# escv1.net
KiCad netlist of a schematic drawn in EAGLE
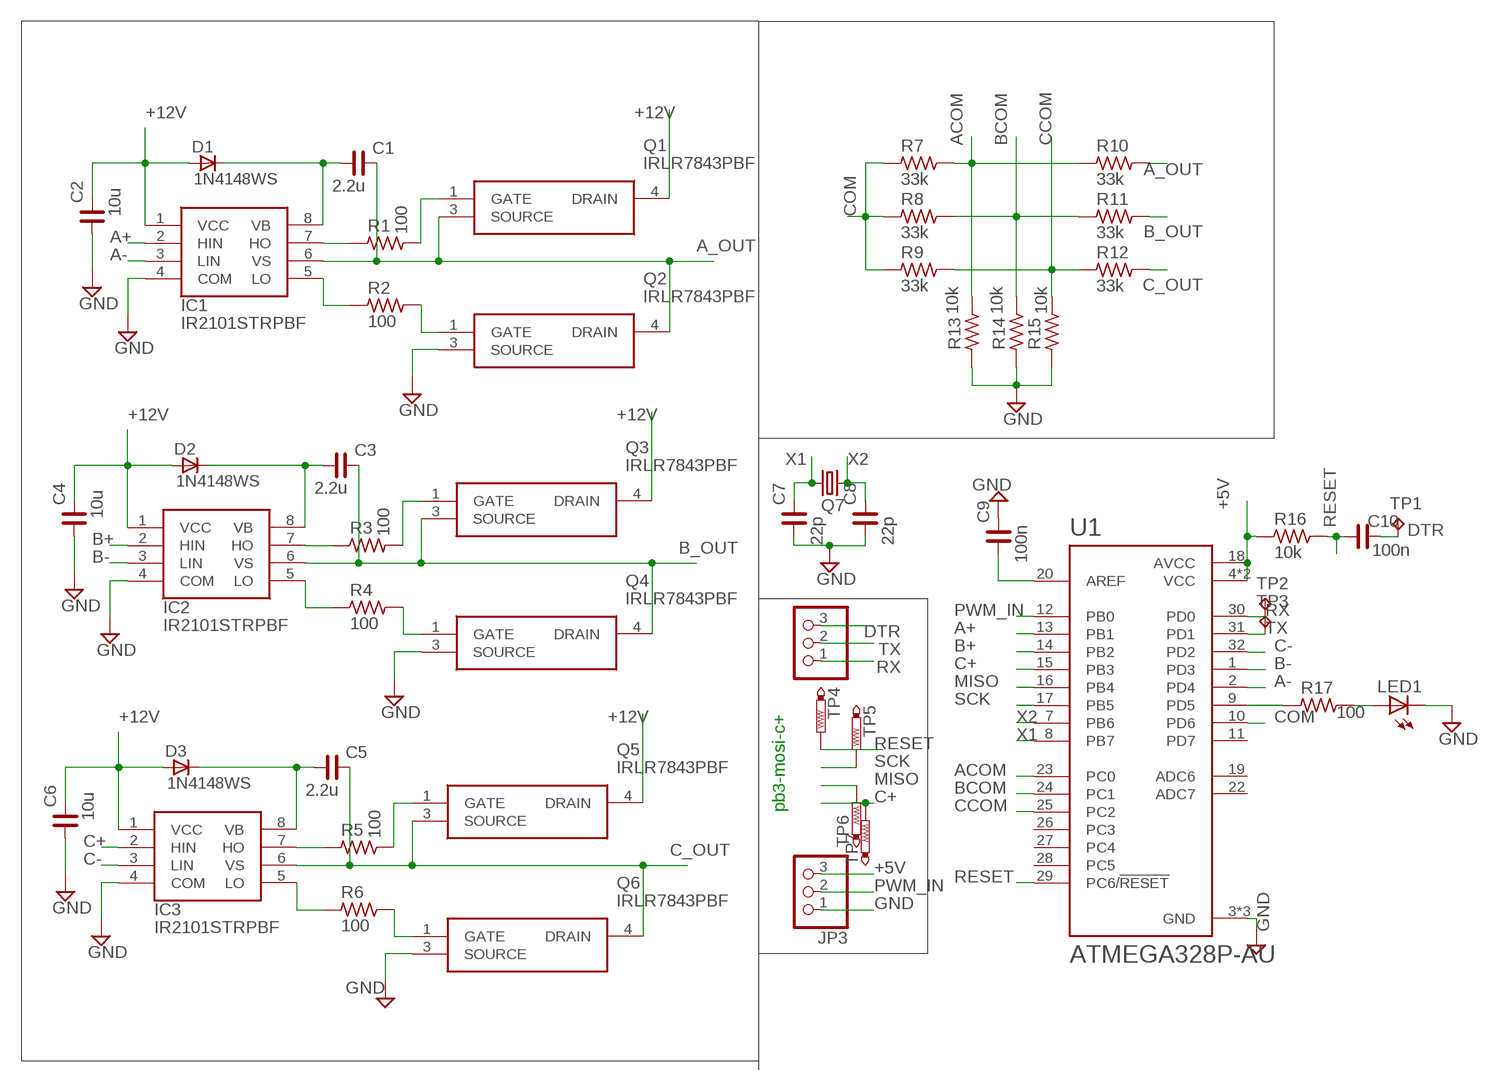
[diagram p0: schematic, sheet 1]

(export (version "E")
  (design (tool "Eeschema 10.0.6"))
  (components
    (comp (ref "C1")
      (value "2.2u")
      (footprint "eagle-import:C2012")
      (libsource (lib "eagle-import") (part "C_2012"))
    )
    (comp (ref "C2")
      (value "10u")
      (footprint "eagle-import:C2012")
      (libsource (lib "eagle-import") (part "C_2012"))
    )
    (comp (ref "C3")
      (value "2.2u")
      (footprint "eagle-import:C2012")
      (libsource (lib "eagle-import") (part "C_2012"))
    )
    (comp (ref "C4")
      (value "10u")
      (footprint "eagle-import:C2012")
      (libsource (lib "eagle-import") (part "C_2012"))
    )
    (comp (ref "C5")
      (value "2.2u")
      (footprint "eagle-import:C2012")
      (libsource (lib "eagle-import") (part "C_2012"))
    )
    (comp (ref "C6")
      (value "10u")
      (footprint "eagle-import:C2012")
      (libsource (lib "eagle-import") (part "C_2012"))
    )
    (comp (ref "C7")
      (value "22p")
      (footprint "eagle-import:C2012")
      (libsource (lib "eagle-import") (part "C_2012"))
    )
    (comp (ref "C8")
      (value "22p")
      (footprint "eagle-import:C2012")
      (libsource (lib "eagle-import") (part "C_2012"))
    )
    (comp (ref "C9")
      (value "100n")
      (footprint "eagle-import:C2012")
      (libsource (lib "eagle-import") (part "C_2012"))
    )
    (comp (ref "C10")
      (value "100n")
      (footprint "eagle-import:C2012")
      (libsource (lib "eagle-import") (part "C_2012"))
    )
    (comp (ref "D1")
      (value "1N4148WS")
      (footprint "eagle-import:SOD323F")
      (libsource (lib "eagle-import") (part "1N4148WS"))
    )
    (comp (ref "D2")
      (value "1N4148WS")
      (footprint "eagle-import:SOD323F")
      (libsource (lib "eagle-import") (part "1N4148WS"))
    )
    (comp (ref "D3")
      (value "1N4148WS")
      (footprint "eagle-import:SOD323F")
      (libsource (lib "eagle-import") (part "1N4148WS"))
    )
    (comp (ref "IC1")
      (value "IR2101STRPBF")
      (footprint "eagle-import:SOIC127P600X175-8N")
      (fields (field (name "MOUSER_PART_NUMBER") "942-IR2101STRPBF"))
      (libsource (lib "eagle-import") (part "IR2101STRPBF"))
    )
    (comp (ref "IC2")
      (value "IR2101STRPBF")
      (footprint "eagle-import:SOIC127P600X175-8N")
      (fields (field (name "MOUSER_PART_NUMBER") "942-IR2101STRPBF"))
      (libsource (lib "eagle-import") (part "IR2101STRPBF"))
    )
    (comp (ref "IC3")
      (value "IR2101STRPBF")
      (footprint "eagle-import:SOIC127P600X175-8N")
      (fields (field (name "MOUSER_PART_NUMBER") "942-IR2101STRPBF"))
      (libsource (lib "eagle-import") (part "IR2101STRPBF"))
    )
    (comp (ref "JP1")
      (value "PINHD-1X3")
      (footprint "eagle-import:1X03")
      (libsource (lib "eagle-import") (part "PINHD-1X3"))
    )
    (comp (ref "JP3")
      (value "PINHD-1X3")
      (footprint "eagle-import:1X03")
      (libsource (lib "eagle-import") (part "PINHD-1X3"))
    )
    (comp (ref "LED1")
      (value "LEDCHIP-LED0805")
      (footprint "eagle-import:CHIP-LED0805")
      (libsource (lib "eagle-import") (part "LEDCHIP-LED0805"))
    )
    (comp (ref "Q1")
      (value "IRLR7843PBF")
      (footprint "eagle-import:D-PAK(TO-252AA)_1")
      (fields (field (name "MOUSER_PART_NUMBER") "942-IRLR7843PBF"))
      (libsource (lib "eagle-import") (part "IRLR7843PBF"))
    )
    (comp (ref "Q2")
      (value "IRLR7843PBF")
      (footprint "eagle-import:D-PAK(TO-252AA)_1")
      (fields (field (name "MOUSER_PART_NUMBER") "942-IRLR7843PBF"))
      (libsource (lib "eagle-import") (part "IRLR7843PBF"))
    )
    (comp (ref "Q3")
      (value "IRLR7843PBF")
      (footprint "eagle-import:D-PAK(TO-252AA)_1")
      (fields (field (name "MOUSER_PART_NUMBER") "942-IRLR7843PBF"))
      (libsource (lib "eagle-import") (part "IRLR7843PBF"))
    )
    (comp (ref "Q4")
      (value "IRLR7843PBF")
      (footprint "eagle-import:D-PAK(TO-252AA)_1")
      (fields (field (name "MOUSER_PART_NUMBER") "942-IRLR7843PBF"))
      (libsource (lib "eagle-import") (part "IRLR7843PBF"))
    )
    (comp (ref "Q5")
      (value "IRLR7843PBF")
      (footprint "eagle-import:D-PAK(TO-252AA)_1")
      (fields (field (name "MOUSER_PART_NUMBER") "942-IRLR7843PBF"))
      (libsource (lib "eagle-import") (part "IRLR7843PBF"))
    )
    (comp (ref "Q6")
      (value "IRLR7843PBF")
      (footprint "eagle-import:D-PAK(TO-252AA)_1")
      (fields (field (name "MOUSER_PART_NUMBER") "942-IRLR7843PBF"))
      (libsource (lib "eagle-import") (part "IRLR7843PBF"))
    )
    (comp (ref "Q7")
      (value "CRYSTALSM49")
      (footprint "eagle-import:SM49")
      (libsource (lib "eagle-import") (part "CRYSTALSM49"))
    )
    (comp (ref "R1")
      (value "100")
      (footprint "eagle-import:R2012")
      (libsource (lib "eagle-import") (part "R_2012"))
    )
    (comp (ref "R2")
      (value "100")
      (footprint "eagle-import:R2012")
      (libsource (lib "eagle-import") (part "R_2012"))
    )
    (comp (ref "R3")
      (value "100")
      (footprint "eagle-import:R2012")
      (libsource (lib "eagle-import") (part "R_2012"))
    )
    (comp (ref "R4")
      (value "100")
      (footprint "eagle-import:R2012")
      (libsource (lib "eagle-import") (part "R_2012"))
    )
    (comp (ref "R5")
      (value "100")
      (footprint "eagle-import:R2012")
      (libsource (lib "eagle-import") (part "R_2012"))
    )
    (comp (ref "R6")
      (value "100")
      (footprint "eagle-import:R2012")
      (libsource (lib "eagle-import") (part "R_2012"))
    )
    (comp (ref "R7")
      (value "33k")
      (footprint "eagle-import:R2012")
      (libsource (lib "eagle-import") (part "R_2012"))
    )
    (comp (ref "R8")
      (value "33k")
      (footprint "eagle-import:R2012")
      (libsource (lib "eagle-import") (part "R_2012"))
    )
    (comp (ref "R9")
      (value "33k")
      (footprint "eagle-import:R2012")
      (libsource (lib "eagle-import") (part "R_2012"))
    )
    (comp (ref "R10")
      (value "33k")
      (footprint "eagle-import:R2012")
      (libsource (lib "eagle-import") (part "R_2012"))
    )
    (comp (ref "R11")
      (value "33k")
      (footprint "eagle-import:R2012")
      (libsource (lib "eagle-import") (part "R_2012"))
    )
    (comp (ref "R12")
      (value "33k")
      (footprint "eagle-import:R2012")
      (libsource (lib "eagle-import") (part "R_2012"))
    )
    (comp (ref "R13")
      (value "10k")
      (footprint "eagle-import:R2012")
      (libsource (lib "eagle-import") (part "R_2012"))
    )
    (comp (ref "R14")
      (value "10k")
      (footprint "eagle-import:R2012")
      (libsource (lib "eagle-import") (part "R_2012"))
    )
    (comp (ref "R15")
      (value "10k")
      (footprint "eagle-import:R2012")
      (libsource (lib "eagle-import") (part "R_2012"))
    )
    (comp (ref "R16")
      (value "10k")
      (footprint "eagle-import:R2012")
      (libsource (lib "eagle-import") (part "R_2012"))
    )
    (comp (ref "R17")
      (value "100")
      (footprint "eagle-import:R2012")
      (libsource (lib "eagle-import") (part "R_2012"))
    )
    (comp (ref "TP1")
      (value "TPTP07R")
      (footprint "eagle-import:TP07R")
      (libsource (lib "eagle-import") (part "TPTP07R"))
    )
    (comp (ref "TP2")
      (value "TPTP07R")
      (footprint "eagle-import:TP07R")
      (libsource (lib "eagle-import") (part "TPTP07R"))
    )
    (comp (ref "TP3")
      (value "TPTP07R")
      (footprint "eagle-import:TP07R")
      (libsource (lib "eagle-import") (part "TPTP07R"))
    )
    (comp (ref "TP4")
      (value "PTR1TP10R")
      (footprint "eagle-import:TP10R")
      (libsource (lib "eagle-import") (part "PTR1TP10R"))
    )
    (comp (ref "TP5")
      (value "PTR1TP10R")
      (footprint "eagle-import:TP10R")
      (libsource (lib "eagle-import") (part "PTR1TP10R"))
    )
    (comp (ref "TP6")
      (value "PTR1TP10R")
      (footprint "eagle-import:TP10R")
      (libsource (lib "eagle-import") (part "PTR1TP10R"))
    )
    (comp (ref "TP7")
      (value "PTR1TP10R")
      (footprint "eagle-import:TP10R")
      (libsource (lib "eagle-import") (part "PTR1TP10R"))
    )
    (comp (ref "U1")
      (value "ATMEGA328P-AU")
      (footprint "eagle-import:QFP80P900X900X120-32N")
      (fields (field (name "MF") "Microchip Technology"))
      (libsource (lib "eagle-import") (part "ATMEGA328P-AU"))
    )
  )
  (nets
    (net (code "1") (name "/+5V") (class "Default")
      (node (ref "JP3") (pin "3") (pinfunction "3_3") (pintype "passive"))
      (node (ref "R16") (pin "1") (pinfunction "1_1") (pintype "passive"))
      (node (ref "U1") (pin "18") (pinfunction "AVCC_18") (pintype "power_in"))
      (node (ref "U1") (pin "4") (pinfunction "VCC_4") (pintype "power_in"))
      (node (ref "U1") (pin "6") (pinfunction "VCC_6") (pintype "power_in"))
    )
    (net (code "2") (name "/+12V") (class "Default")
      (node (ref "C2") (pin "2") (pinfunction "2_2") (pintype "passive"))
      (node (ref "C4") (pin "2") (pinfunction "2_2") (pintype "passive"))
      (node (ref "C6") (pin "2") (pinfunction "2_2") (pintype "passive"))
      (node (ref "D1") (pin "A") (pinfunction "A_A") (pintype "passive"))
      (node (ref "D2") (pin "A") (pinfunction "A_A") (pintype "passive"))
      (node (ref "D3") (pin "A") (pinfunction "A_A") (pintype "passive"))
      (node (ref "IC1") (pin "1") (pinfunction "VCC_1") (pintype "bidirectional"))
      (node (ref "IC2") (pin "1") (pinfunction "VCC_1") (pintype "bidirectional"))
      (node (ref "IC3") (pin "1") (pinfunction "VCC_1") (pintype "bidirectional"))
      (node (ref "Q1") (pin "4") (pinfunction "DRAIN_4") (pintype "bidirectional"))
      (node (ref "Q3") (pin "4") (pinfunction "DRAIN_4") (pintype "bidirectional"))
      (node (ref "Q5") (pin "4") (pinfunction "DRAIN_4") (pintype "bidirectional"))
    )
    (net (code "3") (name "/A+") (class "Default")
      (node (ref "IC1") (pin "2") (pinfunction "HIN_2") (pintype "bidirectional"))
      (node (ref "U1") (pin "13") (pinfunction "PB1_13") (pintype "bidirectional"))
    )
    (net (code "4") (name "/A-") (class "Default")
      (node (ref "IC1") (pin "3") (pinfunction "LIN_3") (pintype "bidirectional"))
      (node (ref "U1") (pin "2") (pinfunction "PD4_2") (pintype "bidirectional"))
    )
    (net (code "5") (name "/ACOM") (class "Default")
      (node (ref "R10") (pin "1") (pinfunction "1_1") (pintype "passive"))
      (node (ref "R13") (pin "2") (pinfunction "2_2") (pintype "passive"))
      (node (ref "R7") (pin "2") (pinfunction "2_2") (pintype "passive"))
      (node (ref "U1") (pin "23") (pinfunction "PC0_23") (pintype "bidirectional"))
    )
    (net (code "6") (name "/A_OUT") (class "Default")
      (node (ref "C1") (pin "2") (pinfunction "2_2") (pintype "passive"))
      (node (ref "IC1") (pin "6") (pinfunction "VS_6") (pintype "bidirectional"))
      (node (ref "Q1") (pin "3") (pinfunction "SOURCE_3") (pintype "bidirectional"))
      (node (ref "Q2") (pin "4") (pinfunction "DRAIN_4") (pintype "bidirectional"))
      (node (ref "R10") (pin "2") (pinfunction "2_2") (pintype "passive"))
    )
    (net (code "7") (name "/B+") (class "Default")
      (node (ref "IC2") (pin "2") (pinfunction "HIN_2") (pintype "bidirectional"))
      (node (ref "U1") (pin "14") (pinfunction "PB2_14") (pintype "bidirectional"))
    )
    (net (code "8") (name "/B-") (class "Default")
      (node (ref "IC2") (pin "3") (pinfunction "LIN_3") (pintype "bidirectional"))
      (node (ref "U1") (pin "1") (pinfunction "PD3_1") (pintype "bidirectional"))
    )
    (net (code "9") (name "/BCOM") (class "Default")
      (node (ref "R11") (pin "1") (pinfunction "1_1") (pintype "passive"))
      (node (ref "R14") (pin "2") (pinfunction "2_2") (pintype "passive"))
      (node (ref "R8") (pin "2") (pinfunction "2_2") (pintype "passive"))
      (node (ref "U1") (pin "24") (pinfunction "PC1_24") (pintype "bidirectional"))
    )
    (net (code "10") (name "/B_OUT") (class "Default")
      (node (ref "C3") (pin "2") (pinfunction "2_2") (pintype "passive"))
      (node (ref "IC2") (pin "6") (pinfunction "VS_6") (pintype "bidirectional"))
      (node (ref "Q3") (pin "3") (pinfunction "SOURCE_3") (pintype "bidirectional"))
      (node (ref "Q4") (pin "4") (pinfunction "DRAIN_4") (pintype "bidirectional"))
      (node (ref "R11") (pin "2") (pinfunction "2_2") (pintype "passive"))
    )
    (net (code "11") (name "/C+") (class "Default")
      (node (ref "IC3") (pin "2") (pinfunction "HIN_2") (pintype "bidirectional"))
      (node (ref "TP7") (pin "TP") (pinfunction "TP_TP") (pintype "input"))
      (node (ref "U1") (pin "15") (pinfunction "PB3_15") (pintype "bidirectional"))
    )
    (net (code "12") (name "/C-") (class "Default")
      (node (ref "IC3") (pin "3") (pinfunction "LIN_3") (pintype "bidirectional"))
      (node (ref "U1") (pin "32") (pinfunction "PD2_32") (pintype "bidirectional"))
    )
    (net (code "13") (name "/CCOM") (class "Default")
      (node (ref "R12") (pin "1") (pinfunction "1_1") (pintype "passive"))
      (node (ref "R15") (pin "2") (pinfunction "2_2") (pintype "passive"))
      (node (ref "R9") (pin "2") (pinfunction "2_2") (pintype "passive"))
      (node (ref "U1") (pin "25") (pinfunction "PC2_25") (pintype "bidirectional"))
    )
    (net (code "14") (name "/COM") (class "Default")
      (node (ref "R7") (pin "1") (pinfunction "1_1") (pintype "passive"))
      (node (ref "R8") (pin "1") (pinfunction "1_1") (pintype "passive"))
      (node (ref "R9") (pin "1") (pinfunction "1_1") (pintype "passive"))
      (node (ref "U1") (pin "10") (pinfunction "PD6_10") (pintype "bidirectional"))
    )
    (net (code "15") (name "/C_OUT") (class "Default")
      (node (ref "C5") (pin "2") (pinfunction "2_2") (pintype "passive"))
      (node (ref "IC3") (pin "6") (pinfunction "VS_6") (pintype "bidirectional"))
      (node (ref "Q5") (pin "3") (pinfunction "SOURCE_3") (pintype "bidirectional"))
      (node (ref "Q6") (pin "4") (pinfunction "DRAIN_4") (pintype "bidirectional"))
      (node (ref "R12") (pin "2") (pinfunction "2_2") (pintype "passive"))
    )
    (net (code "16") (name "/DTR") (class "Default")
      (node (ref "C10") (pin "2") (pinfunction "2_2") (pintype "passive"))
      (node (ref "JP1") (pin "3") (pinfunction "3_3") (pintype "passive"))
      (node (ref "TP1") (pin "TP") (pinfunction "TP_TP") (pintype "input"))
    )
    (net (code "17") (name "/MISO") (class "Default")
      (node (ref "TP6") (pin "TP") (pinfunction "TP_TP") (pintype "input"))
      (node (ref "U1") (pin "16") (pinfunction "PB4_16") (pintype "bidirectional"))
    )
    (net (code "18") (name "/PWM_IN") (class "Default")
      (node (ref "JP3") (pin "2") (pinfunction "2_2") (pintype "passive"))
      (node (ref "U1") (pin "12") (pinfunction "PB0_12") (pintype "bidirectional"))
    )
    (net (code "19") (name "/RESET") (class "Default")
      (node (ref "C10") (pin "1") (pinfunction "1_1") (pintype "passive"))
      (node (ref "R16") (pin "2") (pinfunction "2_2") (pintype "passive"))
      (node (ref "TP4") (pin "TP") (pinfunction "TP_TP") (pintype "input"))
      (node (ref "U1") (pin "29") (pinfunction "PC6/~{RESET}_29") (pintype "bidirectional"))
    )
    (net (code "20") (name "/RX") (class "Default")
      (node (ref "JP1") (pin "1") (pinfunction "1_1") (pintype "passive"))
      (node (ref "TP2") (pin "TP") (pinfunction "TP_TP") (pintype "input"))
      (node (ref "U1") (pin "30") (pinfunction "PD0_30") (pintype "bidirectional"))
    )
    (net (code "21") (name "/SCK") (class "Default")
      (node (ref "TP5") (pin "TP") (pinfunction "TP_TP") (pintype "input"))
      (node (ref "U1") (pin "17") (pinfunction "PB5_17") (pintype "bidirectional"))
    )
    (net (code "22") (name "/TX") (class "Default")
      (node (ref "JP1") (pin "2") (pinfunction "2_2") (pintype "passive"))
      (node (ref "TP3") (pin "TP") (pinfunction "TP_TP") (pintype "input"))
      (node (ref "U1") (pin "31") (pinfunction "PD1_31") (pintype "bidirectional"))
    )
    (net (code "23") (name "/X1") (class "Default")
      (node (ref "C7") (pin "2") (pinfunction "2_2") (pintype "passive"))
      (node (ref "Q7") (pin "1") (pinfunction "1_1") (pintype "passive"))
      (node (ref "U1") (pin "8") (pinfunction "PB7_8") (pintype "bidirectional"))
    )
    (net (code "24") (name "/X2") (class "Default")
      (node (ref "C8") (pin "2") (pinfunction "2_2") (pintype "passive"))
      (node (ref "Q7") (pin "2") (pinfunction "2_2") (pintype "passive"))
      (node (ref "U1") (pin "7") (pinfunction "PB6_7") (pintype "bidirectional"))
    )
    (net (code "25") (name "GND") (class "Default")
      (node (ref "C2") (pin "1") (pinfunction "1_1") (pintype "passive"))
      (node (ref "C4") (pin "1") (pinfunction "1_1") (pintype "passive"))
      (node (ref "C6") (pin "1") (pinfunction "1_1") (pintype "passive"))
      (node (ref "C7") (pin "1") (pinfunction "1_1") (pintype "passive"))
      (node (ref "C8") (pin "1") (pinfunction "1_1") (pintype "passive"))
      (node (ref "C9") (pin "2") (pinfunction "2_2") (pintype "passive"))
      (node (ref "IC1") (pin "4") (pinfunction "COM_4") (pintype "bidirectional"))
      (node (ref "IC2") (pin "4") (pinfunction "COM_4") (pintype "bidirectional"))
      (node (ref "IC3") (pin "4") (pinfunction "COM_4") (pintype "bidirectional"))
      (node (ref "JP3") (pin "1") (pinfunction "1_1") (pintype "passive"))
      (node (ref "LED1") (pin "C") (pinfunction "C_C") (pintype "passive"))
      (node (ref "Q2") (pin "3") (pinfunction "SOURCE_3") (pintype "bidirectional"))
      (node (ref "Q4") (pin "3") (pinfunction "SOURCE_3") (pintype "bidirectional"))
      (node (ref "Q6") (pin "3") (pinfunction "SOURCE_3") (pintype "bidirectional"))
      (node (ref "R13") (pin "1") (pinfunction "1_1") (pintype "passive"))
      (node (ref "R14") (pin "1") (pinfunction "1_1") (pintype "passive"))
      (node (ref "R15") (pin "1") (pinfunction "1_1") (pintype "passive"))
      (node (ref "U1") (pin "21") (pinfunction "GND_21") (pintype "power_in"))
      (node (ref "U1") (pin "3") (pinfunction "GND_3") (pintype "power_in"))
      (node (ref "U1") (pin "5") (pinfunction "GND_5") (pintype "power_in"))
    )
    (net (code "26") (name "Net-(IC1-HO)") (class "Default")
      (node (ref "IC1") (pin "7") (pinfunction "HO_7") (pintype "bidirectional"))
      (node (ref "R1") (pin "1") (pinfunction "1_1") (pintype "passive"))
    )
    (net (code "27") (name "Net-(IC1-LO)") (class "Default")
      (node (ref "IC1") (pin "5") (pinfunction "LO_5") (pintype "bidirectional"))
      (node (ref "R2") (pin "1") (pinfunction "1_1") (pintype "passive"))
    )
    (net (code "28") (name "Net-(IC1-VB)") (class "Default")
      (node (ref "C1") (pin "1") (pinfunction "1_1") (pintype "passive"))
      (node (ref "D1") (pin "C") (pinfunction "C_C") (pintype "passive"))
      (node (ref "IC1") (pin "8") (pinfunction "VB_8") (pintype "bidirectional"))
    )
    (net (code "29") (name "Net-(IC2-HO)") (class "Default")
      (node (ref "IC2") (pin "7") (pinfunction "HO_7") (pintype "bidirectional"))
      (node (ref "R3") (pin "1") (pinfunction "1_1") (pintype "passive"))
    )
    (net (code "30") (name "Net-(IC2-LO)") (class "Default")
      (node (ref "IC2") (pin "5") (pinfunction "LO_5") (pintype "bidirectional"))
      (node (ref "R4") (pin "1") (pinfunction "1_1") (pintype "passive"))
    )
    (net (code "31") (name "Net-(IC2-VB)") (class "Default")
      (node (ref "C3") (pin "1") (pinfunction "1_1") (pintype "passive"))
      (node (ref "D2") (pin "C") (pinfunction "C_C") (pintype "passive"))
      (node (ref "IC2") (pin "8") (pinfunction "VB_8") (pintype "bidirectional"))
    )
    (net (code "32") (name "Net-(IC3-HO)") (class "Default")
      (node (ref "IC3") (pin "7") (pinfunction "HO_7") (pintype "bidirectional"))
      (node (ref "R5") (pin "1") (pinfunction "1_1") (pintype "passive"))
    )
    (net (code "33") (name "Net-(IC3-LO)") (class "Default")
      (node (ref "IC3") (pin "5") (pinfunction "LO_5") (pintype "bidirectional"))
      (node (ref "R6") (pin "1") (pinfunction "1_1") (pintype "passive"))
    )
    (net (code "34") (name "Net-(IC3-VB)") (class "Default")
      (node (ref "C5") (pin "1") (pinfunction "1_1") (pintype "passive"))
      (node (ref "D3") (pin "C") (pinfunction "C_C") (pintype "passive"))
      (node (ref "IC3") (pin "8") (pinfunction "VB_8") (pintype "bidirectional"))
    )
    (net (code "35") (name "Net-(LED1-PadA)") (class "Default")
      (node (ref "LED1") (pin "A") (pinfunction "A_A") (pintype "passive"))
      (node (ref "R17") (pin "2") (pinfunction "2_2") (pintype "passive"))
    )
    (net (code "36") (name "Net-(Q1-GATE)") (class "Default")
      (node (ref "Q1") (pin "1") (pinfunction "GATE_1") (pintype "bidirectional"))
      (node (ref "R1") (pin "2") (pinfunction "2_2") (pintype "passive"))
    )
    (net (code "37") (name "Net-(Q2-GATE)") (class "Default")
      (node (ref "Q2") (pin "1") (pinfunction "GATE_1") (pintype "bidirectional"))
      (node (ref "R2") (pin "2") (pinfunction "2_2") (pintype "passive"))
    )
    (net (code "38") (name "Net-(Q3-GATE)") (class "Default")
      (node (ref "Q3") (pin "1") (pinfunction "GATE_1") (pintype "bidirectional"))
      (node (ref "R3") (pin "2") (pinfunction "2_2") (pintype "passive"))
    )
    (net (code "39") (name "Net-(Q4-GATE)") (class "Default")
      (node (ref "Q4") (pin "1") (pinfunction "GATE_1") (pintype "bidirectional"))
      (node (ref "R4") (pin "2") (pinfunction "2_2") (pintype "passive"))
    )
    (net (code "40") (name "Net-(Q5-GATE)") (class "Default")
      (node (ref "Q5") (pin "1") (pinfunction "GATE_1") (pintype "bidirectional"))
      (node (ref "R5") (pin "2") (pinfunction "2_2") (pintype "passive"))
    )
    (net (code "41") (name "Net-(Q6-GATE)") (class "Default")
      (node (ref "Q6") (pin "1") (pinfunction "GATE_1") (pintype "bidirectional"))
      (node (ref "R6") (pin "2") (pinfunction "2_2") (pintype "passive"))
    )
    (net (code "42") (name "Net-(U1-AREF)") (class "Default")
      (node (ref "C9") (pin "1") (pinfunction "1_1") (pintype "passive"))
      (node (ref "U1") (pin "20") (pinfunction "AREF_20") (pintype "input"))
    )
    (net (code "43") (name "Net-(U1-PD5)") (class "Default")
      (node (ref "R17") (pin "1") (pinfunction "1_1") (pintype "passive"))
      (node (ref "U1") (pin "9") (pinfunction "PD5_9") (pintype "bidirectional"))
    )
    (net (code "44") (name "unconnected-(U1-ADC6-Pad19)") (class "Default")
      (node (ref "U1") (pin "19") (pinfunction "ADC6_19") (pintype "bidirectional"))
    )
    (net (code "45") (name "unconnected-(U1-ADC7-Pad22)") (class "Default")
      (node (ref "U1") (pin "22") (pinfunction "ADC7_22") (pintype "bidirectional"))
    )
    (net (code "46") (name "unconnected-(U1-PC3-Pad26)") (class "Default")
      (node (ref "U1") (pin "26") (pinfunction "PC3_26") (pintype "bidirectional"))
    )
    (net (code "47") (name "unconnected-(U1-PC4-Pad27)") (class "Default")
      (node (ref "U1") (pin "27") (pinfunction "PC4_27") (pintype "bidirectional"))
    )
    (net (code "48") (name "unconnected-(U1-PC5-Pad28)") (class "Default")
      (node (ref "U1") (pin "28") (pinfunction "PC5_28") (pintype "bidirectional"))
    )
    (net (code "49") (name "unconnected-(U1-PD7-Pad11)") (class "Default")
      (node (ref "U1") (pin "11") (pinfunction "PD7_11") (pintype "bidirectional"))
    )
  )
)
